# LAUNCHXL-F28069_B_1400922_2.net
KiCad netlist of a schematic drawn in Altium Designer
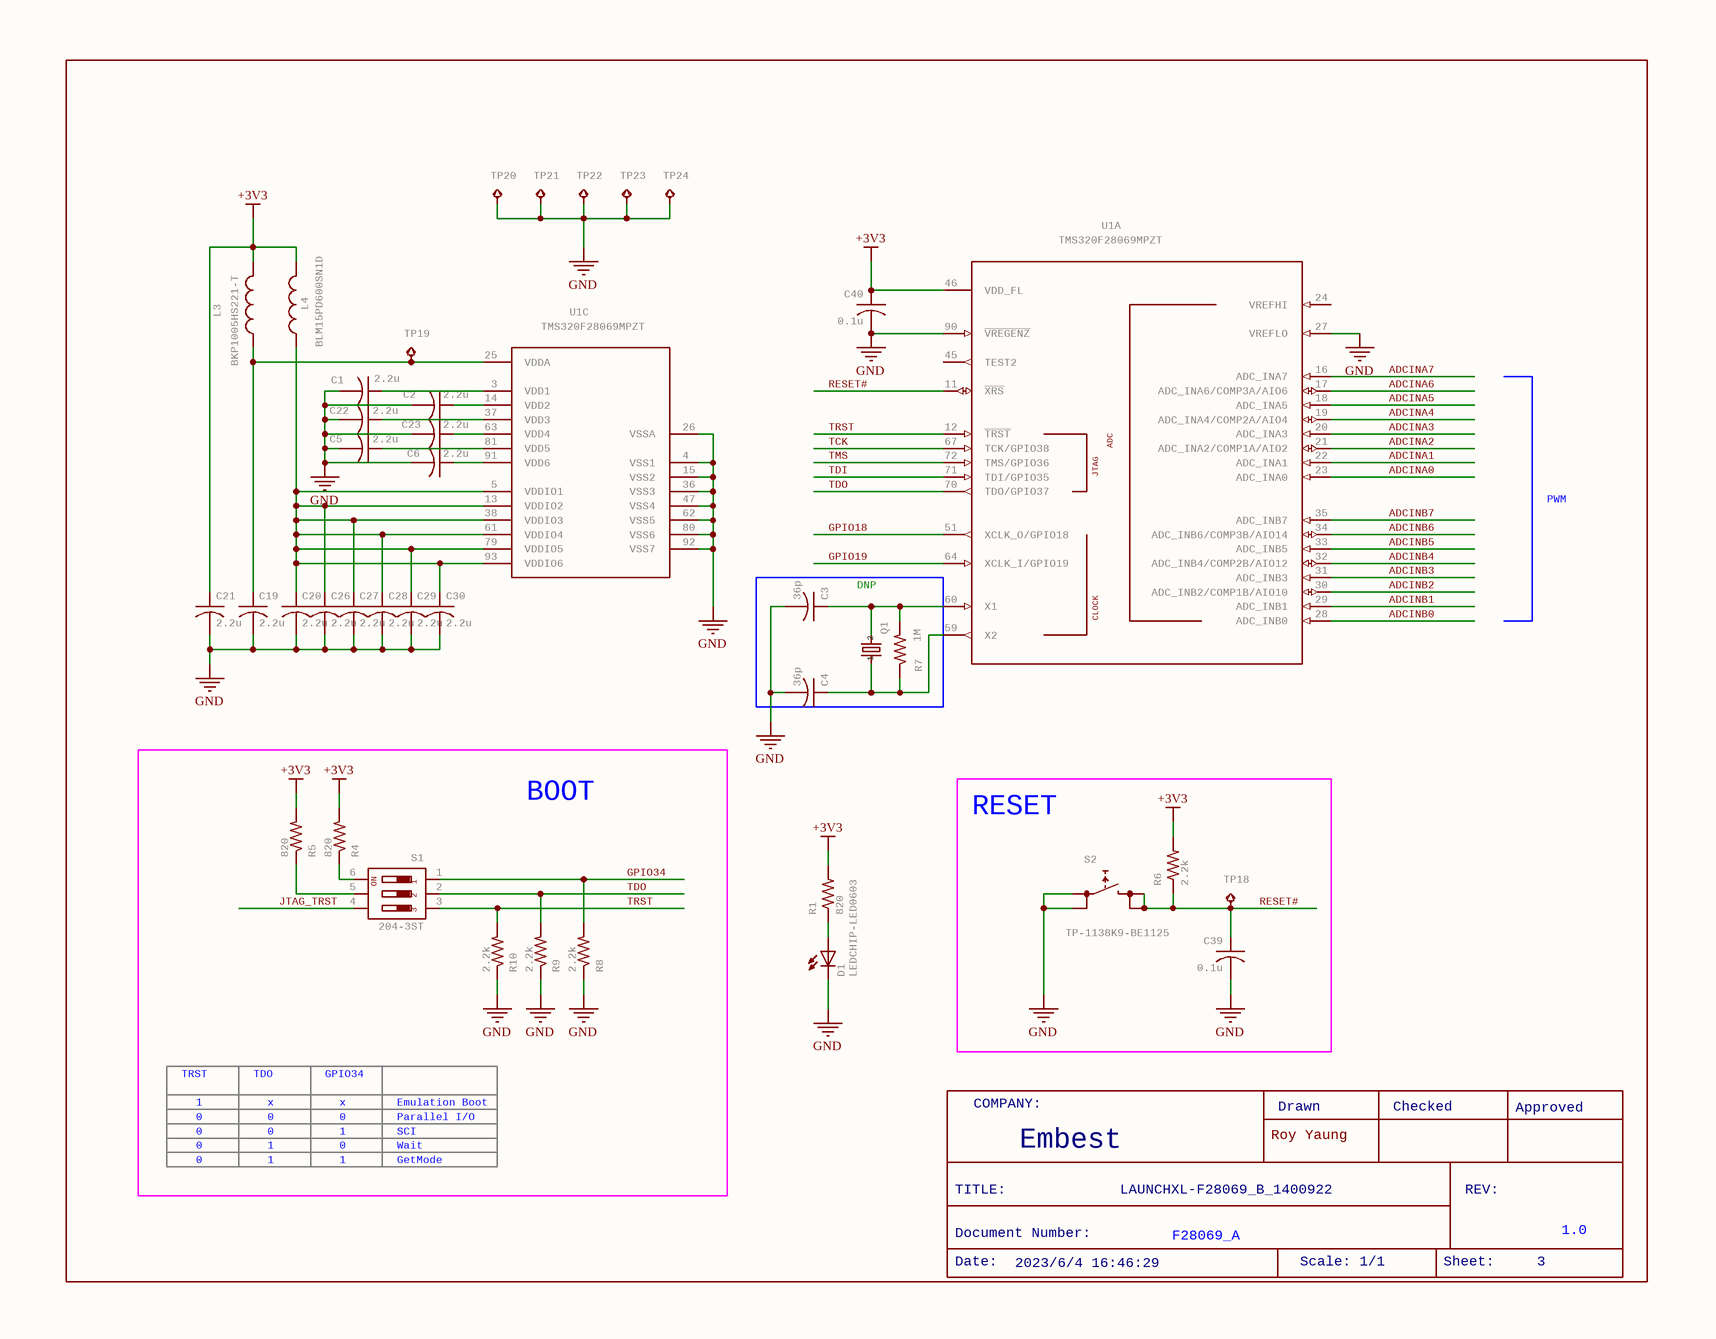
[diagram p0: LAUNCHXL-F28069_B_1400922_2.SchDoc]

(export (version "E")
  (design (tool "Eeschema 10.0.6"))
  (components
    (comp (ref "C1")
      (value "2.2u")
      (footprint "C0402")
      (description "CAPACITOR, American symbol")
      (libsource (lib "rcl") (part "C-USC0402"))
    )
    (comp (ref "C2")
      (value "2.2u")
      (footprint "C0402")
      (description "CAPACITOR, American symbol")
      (libsource (lib "rcl") (part "C-USC0402"))
    )
    (comp (ref "C3")
      (value "36p")
      (footprint "C0402")
      (description "CAPACITOR, American symbol")
      (libsource (lib "") (part "C-USC0402_1"))
    )
    (comp (ref "C4")
      (value "36p")
      (footprint "C0402")
      (description "CAPACITOR, American symbol")
      (libsource (lib "") (part "C-USC0402_1"))
    )
    (comp (ref "C5")
      (value "2.2u")
      (footprint "C0402")
      (description "CAPACITOR, American symbol")
      (libsource (lib "rcl") (part "C-USC0402"))
    )
    (comp (ref "C6")
      (value "2.2u")
      (footprint "C0402")
      (description "CAPACITOR, American symbol")
      (libsource (lib "rcl") (part "C-USC0402"))
    )
    (comp (ref "C19")
      (value "2.2u")
      (footprint "C0402")
      (description "CAPACITOR, American symbol")
      (libsource (lib "rcl") (part "C-USC0402"))
    )
    (comp (ref "C20")
      (value "2.2u")
      (footprint "C0402")
      (description "CAPACITOR, American symbol")
      (libsource (lib "rcl") (part "C-USC0402"))
    )
    (comp (ref "C21")
      (value "2.2u")
      (footprint "C0402")
      (description "CAPACITOR, American symbol")
      (libsource (lib "rcl") (part "C-USC0402"))
    )
    (comp (ref "C22")
      (value "2.2u")
      (footprint "C0402")
      (description "CAPACITOR, American symbol")
      (libsource (lib "rcl") (part "C-USC0402"))
    )
    (comp (ref "C23")
      (value "2.2u")
      (footprint "C0402")
      (description "CAPACITOR, American symbol")
      (libsource (lib "rcl") (part "C-USC0402"))
    )
    (comp (ref "C26")
      (value "2.2u")
      (footprint "C0402")
      (description "CAPACITOR, American symbol")
      (libsource (lib "rcl") (part "C-USC0402"))
    )
    (comp (ref "C27")
      (value "2.2u")
      (footprint "C0402")
      (description "CAPACITOR, American symbol")
      (libsource (lib "rcl") (part "C-USC0402"))
    )
    (comp (ref "C28")
      (value "2.2u")
      (footprint "C0402")
      (description "CAPACITOR, American symbol")
      (libsource (lib "rcl") (part "C-USC0402"))
    )
    (comp (ref "C29")
      (value "2.2u")
      (footprint "C0402")
      (description "CAPACITOR, American symbol")
      (libsource (lib "rcl") (part "C-USC0402"))
    )
    (comp (ref "C30")
      (value "2.2u")
      (footprint "C0402")
      (description "CAPACITOR, American symbol")
      (libsource (lib "rcl") (part "C-USC0402"))
    )
    (comp (ref "C39")
      (value "0.1u")
      (footprint "C0402")
      (description "CAPACITOR, American symbol")
      (libsource (lib "") (part "C-USC0402_1"))
    )
    (comp (ref "C40")
      (value "0.1u")
      (footprint "C0402")
      (description "CAPACITOR, American symbol")
      (libsource (lib "") (part "C-USC0402_1"))
    )
    (comp (ref "D1")
      (value "LEDCHIP-LED0603")
      (footprint "CHIP-LED0603")
      (libsource (lib "led") (part "LEDCHIP-LED0603"))
    )
    (comp (ref "L3")
      (value "BKP1005HS221-T")
      (footprint "R0402")
      (description "INDUCTOR, American symbol")
      (libsource (lib "rcl") (part "L-US0402"))
    )
    (comp (ref "L4")
      (value "BLM15PD600SN1D")
      (footprint "R0402")
      (description "INDUCTOR, American symbol")
      (libsource (lib "rcl") (part "L-US0402"))
    )
    (comp (ref "Q1")
      (value "CRYSTALHC49S")
      (footprint "HC49/S")
      (description "CRYSTAL")
      (fields
        (field (name "1") "1")
        (field (name "2") "2")
        (field (name "MF") "MF")
        (field (name "MPN") "MPN")
      )
      (libsource (lib "crystal") (part "CRYSTALHC49S"))
    )
    (comp (ref "R1")
      (value "820")
      (footprint "R0402")
      (description "RESISTOR, American symbol")
      (libsource (lib "rcl") (part "R-US_R0402"))
    )
    (comp (ref "R4")
      (value "820")
      (footprint "R0402")
      (description "RESISTOR, American symbol")
      (libsource (lib "rcl") (part "R-US_R0402"))
    )
    (comp (ref "R5")
      (value "820")
      (footprint "R0402")
      (description "RESISTOR, American symbol")
      (libsource (lib "rcl") (part "R-US_R0402"))
    )
    (comp (ref "R6")
      (value "2.2k")
      (footprint "R0402")
      (description "RESISTOR, American symbol")
      (libsource (lib "rcl") (part "R-US_R0402"))
    )
    (comp (ref "R7")
      (value "1M")
      (footprint "R0402")
      (description "RESISTOR, American symbol")
      (libsource (lib "rcl") (part "R-US_R0402"))
    )
    (comp (ref "R8")
      (value "2.2k")
      (footprint "R0402")
      (description "RESISTOR, American symbol")
      (libsource (lib "rcl") (part "R-US_R0402"))
    )
    (comp (ref "R9")
      (value "2.2k")
      (footprint "R0402")
      (description "RESISTOR, American symbol")
      (libsource (lib "rcl") (part "R-US_R0402"))
    )
    (comp (ref "R10")
      (value "2.2k")
      (footprint "R0402")
      (description "RESISTOR, American symbol")
      (libsource (lib "rcl") (part "R-US_R0402"))
    )
    (comp (ref "S1")
      (value "204-3ST")
      (footprint "CTS-219-03")
      (description "Surface Mount DIP Switch Series 219 SMT   CTS Electronic Components Sourc: www.ctscorp.com")
      (fields
        (field (name "1") "1")
        (field (name "2") "2")
        (field (name "3") "3")
        (field (name "ON") "ON")
        (field (name "MF") "MF")
        (field (name "MPN") "MPN")
        (field (name "LIBRARYNAME") "switch-dil")
      )
      (libsource (lib "switch-dil") (part "219-03*"))
    )
    (comp (ref "S2")
      (value "TP-1138K9-BE1125")
      (footprint "FSMJSMA")
      (libsource (lib "switch") (part "FSMJSMA"))
    )
    (comp (ref "TP18")
      (value "TESTPAD_TPB1,27")
      (footprint "TESTPAD_B1,27")
      (description "Test pad")
      (fields (field (name "LIBRARYNAME") "RF430FRL152H_EVM_a"))
      (libsource (lib "RF430FRL152H_EVM_a") (part "TESTPAD_TPB1,27"))
    )
    (comp (ref "TP19")
      (value "TESTPAD_TPB1,27")
      (footprint "TESTPAD_B1,27")
      (description "Test pad")
      (fields (field (name "LIBRARYNAME") "RF430FRL152H_EVM_a"))
      (libsource (lib "RF430FRL152H_EVM_a") (part "TESTPAD_TPB1,27"))
    )
    (comp (ref "TP20")
      (value "TESTPAD_TPB1,27")
      (footprint "TESTPAD_B1,27")
      (description "Test pad")
      (fields (field (name "LIBRARYNAME") "RF430FRL152H_EVM_a"))
      (libsource (lib "RF430FRL152H_EVM_a") (part "TESTPAD_TPB1,27"))
    )
    (comp (ref "TP21")
      (value "TESTPAD_TPB1,27")
      (footprint "TESTPAD_B1,27")
      (description "Test pad")
      (fields (field (name "LIBRARYNAME") "RF430FRL152H_EVM_a"))
      (libsource (lib "RF430FRL152H_EVM_a") (part "TESTPAD_TPB1,27"))
    )
    (comp (ref "TP22")
      (value "TESTPAD_TPB1,27")
      (footprint "TESTPAD_B1,27")
      (description "Test pad")
      (fields (field (name "LIBRARYNAME") "RF430FRL152H_EVM_a"))
      (libsource (lib "RF430FRL152H_EVM_a") (part "TESTPAD_TPB1,27"))
    )
    (comp (ref "TP23")
      (value "TESTPAD_TPB1,27")
      (footprint "TESTPAD_B1,27")
      (description "Test pad")
      (fields (field (name "LIBRARYNAME") "RF430FRL152H_EVM_a"))
      (libsource (lib "RF430FRL152H_EVM_a") (part "TESTPAD_TPB1,27"))
    )
    (comp (ref "TP24")
      (value "TESTPAD_TPB1,27")
      (footprint "TESTPAD_B1,27")
      (description "Test pad")
      (fields (field (name "LIBRARYNAME") "RF430FRL152H_EVM_a"))
      (libsource (lib "RF430FRL152H_EVM_a") (part "TESTPAD_TPB1,27"))
    )
    (comp (ref "U1")
      (value "TMS320F28069MPZT")
      (footprint "PQFP100")
      (fields (field (name "JTAG") "JTAG") (field (name "CLOCK") "CLOCK") (field (name "ADC") "ADC"))
      (libsource (lib "LAUNCHXL-F28027") (part "TMS320F28069PZSR"))
    )
  )
  (nets
    (net (code "1") (name "+3V3") (class "Default")
      (node (ref "C21") (pin "1") (pinfunction "1_1") (pintype "passive"))
      (node (ref "C40") (pin "1") (pinfunction "1_1") (pintype "passive"))
      (node (ref "L3") (pin "2") (pinfunction "2_2") (pintype "passive"))
      (node (ref "L4") (pin "2") (pinfunction "2_2") (pintype "passive"))
      (node (ref "R1") (pin "2") (pinfunction "2_2") (pintype "passive"))
      (node (ref "R4") (pin "2") (pinfunction "2_2") (pintype "passive"))
      (node (ref "R5") (pin "2") (pinfunction "2_2") (pintype "passive"))
      (node (ref "R6") (pin "2") (pinfunction "2_2") (pintype "passive"))
      (node (ref "U1") (pin "46") (pinfunction "VDD_FL_46") (pintype "power_in"))
    )
    (net (code "2") (name "/ADCINA0") (class "Default")
      (node (ref "U1") (pin "23") (pinfunction "ADC_INA0_23") (pintype "input"))
    )
    (net (code "3") (name "/ADCINA1") (class "Default")
      (node (ref "U1") (pin "22") (pinfunction "ADC_INA1_22") (pintype "input"))
    )
    (net (code "4") (name "/ADCINA2") (class "Default")
      (node (ref "U1") (pin "21") (pinfunction "ADC_INA2/COMP1A/AIO2_21") (pintype "bidirectional"))
    )
    (net (code "5") (name "/ADCINA3") (class "Default")
      (node (ref "U1") (pin "20") (pinfunction "ADC_INA3_20") (pintype "input"))
    )
    (net (code "6") (name "/ADCINA4") (class "Default")
      (node (ref "U1") (pin "19") (pinfunction "ADC_INA4/COMP2A/AIO4_19") (pintype "bidirectional"))
    )
    (net (code "7") (name "/ADCINA5") (class "Default")
      (node (ref "U1") (pin "18") (pinfunction "ADC_INA5_18") (pintype "input"))
    )
    (net (code "8") (name "/ADCINA6") (class "Default")
      (node (ref "U1") (pin "17") (pinfunction "ADC_INA6/COMP3A/AIO6_17") (pintype "bidirectional"))
    )
    (net (code "9") (name "/ADCINA7") (class "Default")
      (node (ref "U1") (pin "16") (pinfunction "ADC_INA7_16") (pintype "input"))
    )
    (net (code "10") (name "/ADCINB0") (class "Default")
      (node (ref "U1") (pin "28") (pinfunction "ADC_INB0_28") (pintype "input"))
    )
    (net (code "11") (name "/ADCINB1") (class "Default")
      (node (ref "U1") (pin "29") (pinfunction "ADC_INB1_29") (pintype "input"))
    )
    (net (code "12") (name "/ADCINB2") (class "Default")
      (node (ref "U1") (pin "30") (pinfunction "ADC_INB2/COMP1B/AIO10_30") (pintype "bidirectional"))
    )
    (net (code "13") (name "/ADCINB3") (class "Default")
      (node (ref "U1") (pin "31") (pinfunction "ADC_INB3_31") (pintype "input"))
    )
    (net (code "14") (name "/ADCINB4") (class "Default")
      (node (ref "U1") (pin "32") (pinfunction "ADC_INB4/COMP2B/AIO12_32") (pintype "bidirectional"))
    )
    (net (code "15") (name "/ADCINB5") (class "Default")
      (node (ref "U1") (pin "33") (pinfunction "ADC_INB5_33") (pintype "input"))
    )
    (net (code "16") (name "/ADCINB6") (class "Default")
      (node (ref "U1") (pin "34") (pinfunction "ADC_INB6/COMP3B/AIO14_34") (pintype "bidirectional"))
    )
    (net (code "17") (name "/ADCINB7") (class "Default")
      (node (ref "U1") (pin "35") (pinfunction "ADC_INB7_35") (pintype "input"))
    )
    (net (code "18") (name "/GPIO18") (class "Default")
      (node (ref "U1") (pin "51") (pinfunction "XCLK_O/GPIO18_51") (pintype "output"))
    )
    (net (code "19") (name "/GPIO19") (class "Default")
      (node (ref "U1") (pin "64") (pinfunction "XCLK_I/GPIO19_64") (pintype "input"))
    )
    (net (code "20") (name "/GPIO34") (class "Default")
      (node (ref "R8") (pin "2") (pinfunction "2_2") (pintype "passive"))
      (node (ref "S1") (pin "1") (pinfunction "1_1") (pintype "passive"))
    )
    (net (code "21") (name "/JTAG_TRST") (class "Default")
      (node (ref "S1") (pin "4") (pinfunction "4_4") (pintype "passive"))
    )
    (net (code "22") (name "/RESET#") (class "Default")
      (node (ref "C39") (pin "1") (pinfunction "1_1") (pintype "passive"))
      (node (ref "R6") (pin "1") (pinfunction "1_1") (pintype "passive"))
      (node (ref "S2") (pin "P$3") (pinfunction "1_P$3") (pintype "passive"))
      (node (ref "S2") (pin "P$4") (pinfunction "1_P$4") (pintype "passive"))
      (node (ref "TP18") (pin "TP") (pinfunction "TP_TP") (pintype "input"))
      (node (ref "U1") (pin "11") (pinfunction "~{XRS}_11") (pintype "bidirectional"))
    )
    (net (code "23") (name "/TCK") (class "Default")
      (node (ref "U1") (pin "67") (pinfunction "TCK/GPIO38_67") (pintype "input"))
    )
    (net (code "24") (name "/TDI") (class "Default")
      (node (ref "U1") (pin "71") (pinfunction "TDI/GPIO35_71") (pintype "input"))
    )
    (net (code "25") (name "/TDO") (class "Default")
      (node (ref "R9") (pin "2") (pinfunction "2_2") (pintype "passive"))
      (node (ref "S1") (pin "2") (pinfunction "2_2") (pintype "passive"))
      (node (ref "U1") (pin "70") (pinfunction "TDO/GPIO37_70") (pintype "output"))
    )
    (net (code "26") (name "/TMS") (class "Default")
      (node (ref "U1") (pin "72") (pinfunction "TMS/GPIO36_72") (pintype "input"))
    )
    (net (code "27") (name "/TRST") (class "Default")
      (node (ref "R10") (pin "2") (pinfunction "2_2") (pintype "passive"))
      (node (ref "S1") (pin "3") (pinfunction "3_3") (pintype "passive"))
      (node (ref "U1") (pin "12") (pinfunction "~{TRST}_12") (pintype "input"))
    )
    (net (code "28") (name "GND") (class "Default")
      (node (ref "C1") (pin "2") (pinfunction "2_2") (pintype "passive"))
      (node (ref "C19") (pin "2") (pinfunction "2_2") (pintype "passive"))
      (node (ref "C2") (pin "2") (pinfunction "2_2") (pintype "passive"))
      (node (ref "C20") (pin "2") (pinfunction "2_2") (pintype "passive"))
      (node (ref "C21") (pin "2") (pinfunction "2_2") (pintype "passive"))
      (node (ref "C22") (pin "2") (pinfunction "2_2") (pintype "passive"))
      (node (ref "C23") (pin "2") (pinfunction "2_2") (pintype "passive"))
      (node (ref "C26") (pin "2") (pinfunction "2_2") (pintype "passive"))
      (node (ref "C27") (pin "2") (pinfunction "2_2") (pintype "passive"))
      (node (ref "C28") (pin "2") (pinfunction "2_2") (pintype "passive"))
      (node (ref "C29") (pin "2") (pinfunction "2_2") (pintype "passive"))
      (node (ref "C3") (pin "2") (pinfunction "2_2") (pintype "passive"))
      (node (ref "C30") (pin "2") (pinfunction "2_2") (pintype "passive"))
      (node (ref "C39") (pin "2") (pinfunction "2_2") (pintype "passive"))
      (node (ref "C4") (pin "2") (pinfunction "2_2") (pintype "passive"))
      (node (ref "C40") (pin "2") (pinfunction "2_2") (pintype "passive"))
      (node (ref "C5") (pin "2") (pinfunction "2_2") (pintype "passive"))
      (node (ref "C6") (pin "2") (pinfunction "2_2") (pintype "passive"))
      (node (ref "D1") (pin "C") (pinfunction "C_C") (pintype "passive"))
      (node (ref "R10") (pin "1") (pinfunction "1_1") (pintype "passive"))
      (node (ref "R8") (pin "1") (pinfunction "1_1") (pintype "passive"))
      (node (ref "R9") (pin "1") (pinfunction "1_1") (pintype "passive"))
      (node (ref "S2") (pin "P$1") (pinfunction "0_P$1") (pintype "passive"))
      (node (ref "S2") (pin "P$2") (pinfunction "0_P$2") (pintype "passive"))
      (node (ref "TP20") (pin "TP") (pinfunction "TP_TP") (pintype "input"))
      (node (ref "TP21") (pin "TP") (pinfunction "TP_TP") (pintype "input"))
      (node (ref "TP22") (pin "TP") (pinfunction "TP_TP") (pintype "input"))
      (node (ref "TP23") (pin "TP") (pinfunction "TP_TP") (pintype "input"))
      (node (ref "TP24") (pin "TP") (pinfunction "TP_TP") (pintype "input"))
      (node (ref "U1") (pin "15") (pinfunction "VSS2_15") (pintype "power_in"))
      (node (ref "U1") (pin "26") (pinfunction "VSSA_26") (pintype "power_in"))
      (node (ref "U1") (pin "27") (pinfunction "VREFLO_27") (pintype "input"))
      (node (ref "U1") (pin "36") (pinfunction "VSS3_36") (pintype "power_in"))
      (node (ref "U1") (pin "4") (pinfunction "VSS1_4") (pintype "power_in"))
      (node (ref "U1") (pin "47") (pinfunction "VSS4_47") (pintype "power_in"))
      (node (ref "U1") (pin "62") (pinfunction "VSS5_62") (pintype "power_in"))
      (node (ref "U1") (pin "80") (pinfunction "VSS6_80") (pintype "power_in"))
      (node (ref "U1") (pin "90") (pinfunction "~{VREGENZ}_90") (pintype "input"))
      (node (ref "U1") (pin "92") (pinfunction "VSS7_92") (pintype "power_in"))
    )
    (net (code "29") (name "Net-(D1-PadA)") (class "Default")
      (node (ref "D1") (pin "A") (pinfunction "A_A") (pintype "passive"))
      (node (ref "R1") (pin "1") (pinfunction "1_1") (pintype "passive"))
    )
    (net (code "30") (name "Net-(R4-Pad1)") (class "Default")
      (node (ref "R4") (pin "1") (pinfunction "1_1") (pintype "passive"))
      (node (ref "S1") (pin "6") (pinfunction "6_6") (pintype "passive"))
    )
    (net (code "31") (name "Net-(R5-Pad1)") (class "Default")
      (node (ref "R5") (pin "1") (pinfunction "1_1") (pintype "passive"))
      (node (ref "S1") (pin "5") (pinfunction "5_5") (pintype "passive"))
    )
    (net (code "32") (name "Net-(U1A-X1)") (class "Default")
      (node (ref "C3") (pin "1") (pinfunction "1_1") (pintype "passive"))
      (node (ref "Q1") (pin "2") (pinfunction "2_2") (pintype "passive"))
      (node (ref "R7") (pin "2") (pinfunction "2_2") (pintype "passive"))
      (node (ref "U1") (pin "60") (pinfunction "X1_60") (pintype "input"))
    )
    (net (code "33") (name "Net-(U1A-X2)") (class "Default")
      (node (ref "C4") (pin "1") (pinfunction "1_1") (pintype "passive"))
      (node (ref "Q1") (pin "1") (pinfunction "1_1") (pintype "passive"))
      (node (ref "R7") (pin "1") (pinfunction "1_1") (pintype "passive"))
      (node (ref "U1") (pin "59") (pinfunction "X2_59") (pintype "output"))
    )
    (net (code "34") (name "Net-(U1C-VDD1)") (class "Default")
      (node (ref "C1") (pin "1") (pinfunction "1_1") (pintype "passive"))
      (node (ref "U1") (pin "3") (pinfunction "VDD1_3") (pintype "power_in"))
    )
    (net (code "35") (name "Net-(U1C-VDD2)") (class "Default")
      (node (ref "C2") (pin "1") (pinfunction "1_1") (pintype "passive"))
      (node (ref "U1") (pin "14") (pinfunction "VDD2_14") (pintype "power_in"))
    )
    (net (code "36") (name "Net-(U1C-VDD3)") (class "Default")
      (node (ref "C22") (pin "1") (pinfunction "1_1") (pintype "passive"))
      (node (ref "U1") (pin "37") (pinfunction "VDD3_37") (pintype "power_in"))
    )
    (net (code "37") (name "Net-(U1C-VDD4)") (class "Default")
      (node (ref "C23") (pin "1") (pinfunction "1_1") (pintype "passive"))
      (node (ref "U1") (pin "63") (pinfunction "VDD4_63") (pintype "power_in"))
    )
    (net (code "38") (name "Net-(U1C-VDD5)") (class "Default")
      (node (ref "C5") (pin "1") (pinfunction "1_1") (pintype "passive"))
      (node (ref "U1") (pin "81") (pinfunction "VDD5_81") (pintype "power_in"))
    )
    (net (code "39") (name "Net-(U1C-VDD6)") (class "Default")
      (node (ref "C6") (pin "1") (pinfunction "1_1") (pintype "passive"))
      (node (ref "U1") (pin "91") (pinfunction "VDD6_91") (pintype "power_in"))
    )
    (net (code "40") (name "Net-(U1C-VDDA)") (class "Default")
      (node (ref "C19") (pin "1") (pinfunction "1_1") (pintype "passive"))
      (node (ref "L3") (pin "1") (pinfunction "1_1") (pintype "passive"))
      (node (ref "TP19") (pin "TP") (pinfunction "TP_TP") (pintype "input"))
      (node (ref "U1") (pin "25") (pinfunction "VDDA_25") (pintype "power_in"))
    )
    (net (code "41") (name "Net-(U1C-VDDIO1)") (class "Default")
      (node (ref "C20") (pin "1") (pinfunction "1_1") (pintype "passive"))
      (node (ref "C26") (pin "1") (pinfunction "1_1") (pintype "passive"))
      (node (ref "C27") (pin "1") (pinfunction "1_1") (pintype "passive"))
      (node (ref "C28") (pin "1") (pinfunction "1_1") (pintype "passive"))
      (node (ref "C29") (pin "1") (pinfunction "1_1") (pintype "passive"))
      (node (ref "C30") (pin "1") (pinfunction "1_1") (pintype "passive"))
      (node (ref "L4") (pin "1") (pinfunction "1_1") (pintype "passive"))
      (node (ref "U1") (pin "13") (pinfunction "VDDIO2_13") (pintype "power_in"))
      (node (ref "U1") (pin "38") (pinfunction "VDDIO3_38") (pintype "power_in"))
      (node (ref "U1") (pin "5") (pinfunction "VDDIO1_5") (pintype "power_in"))
      (node (ref "U1") (pin "61") (pinfunction "VDDIO4_61") (pintype "power_in"))
      (node (ref "U1") (pin "79") (pinfunction "VDDIO5_79") (pintype "power_in"))
      (node (ref "U1") (pin "93") (pinfunction "VDDIO6_93") (pintype "power_in"))
    )
    (net (code "42") (name "unconnected-(U1A-TEST2-Pad45)") (class "Default")
      (node (ref "U1") (pin "45") (pinfunction "TEST2_45") (pintype "output"))
    )
    (net (code "43") (name "unconnected-(U1A-VREFHI-Pad24)") (class "Default")
      (node (ref "U1") (pin "24") (pinfunction "VREFHI_24") (pintype "input"))
    )
  )
)
